# WallPhish.net
KiCad netlist of a schematic drawn in Altium Designer
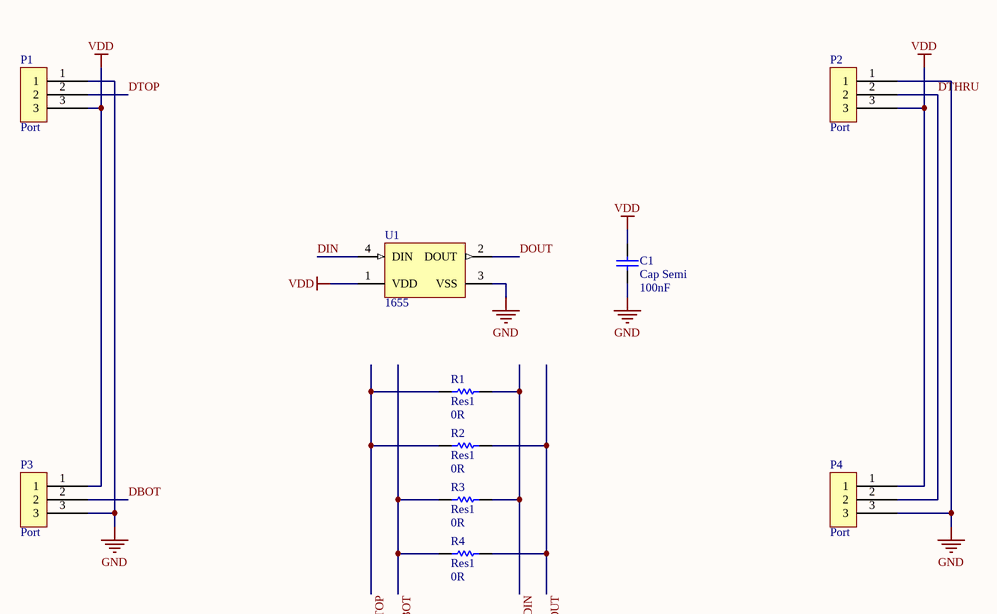
[diagram p0: WallPhish.SchDoc]

(export (version "E")
  (design (tool "Eeschema 10.0.6"))
  (components
    (comp (ref "C1")
      (value "Cap Semi")
      (footprint "C1206")
      (description "Capacitor (Semiconductor SIM Model)")
      (fields (field (name "ALTIUM_VALUE") "100nF") (field (name "PUBLISHER") "Altium Limited"))
      (libsource (lib "Miscellaneous Devices") (part "Cap Semi"))
    )
    (comp (ref "P1")
      (value "Port")
      (footprint "Port-3wire")
      (description "3-wire port")
      (libsource (lib "Port-3wire") (part "Port"))
    )
    (comp (ref "P2")
      (value "Port")
      (footprint "Port-3wire")
      (description "3-wire port")
      (libsource (lib "Port-3wire") (part "Port"))
    )
    (comp (ref "P3")
      (value "Port")
      (footprint "Port-3wire")
      (description "3-wire port")
      (libsource (lib "Port-3wire") (part "Port"))
    )
    (comp (ref "P4")
      (value "Port")
      (footprint "Port-3wire")
      (description "3-wire port")
      (libsource (lib "Port-3wire") (part "Port"))
    )
    (comp (ref "R1")
      (value "Res1")
      (footprint "C1206")
      (description "Resistor")
      (fields (field (name "ALTIUM_VALUE") "0R") (field (name "PUBLISHER") "Altium Limited"))
      (libsource (lib "Miscellaneous Devices") (part "Res1"))
    )
    (comp (ref "R2")
      (value "Res1")
      (footprint "C1206")
      (description "Resistor")
      (fields (field (name "ALTIUM_VALUE") "0R") (field (name "PUBLISHER") "Altium Limited"))
      (libsource (lib "Miscellaneous Devices") (part "Res1"))
    )
    (comp (ref "R3")
      (value "Res1")
      (footprint "C1206")
      (description "Resistor")
      (fields (field (name "ALTIUM_VALUE") "0R") (field (name "PUBLISHER") "Altium Limited"))
      (libsource (lib "Miscellaneous Devices") (part "Res1"))
    )
    (comp (ref "R4")
      (value "Res1")
      (footprint "C1206")
      (description "Resistor")
      (fields (field (name "ALTIUM_VALUE") "0R") (field (name "PUBLISHER") "Altium Limited"))
      (libsource (lib "Miscellaneous Devices") (part "Res1"))
    )
    (comp (ref "U1")
      (value "1655")
      (footprint "ADA-RGB-1655_V")
      (fields (field (name "MANUFACTURER") "Adafruit-Industries-LLC"))
      (libsource (lib "Altium Content Vault") (part "ADA-RGB-1655-4"))
    )
  )
  (nets
    (net (code "1") (name "/DBOT") (class "Default")
      (node (ref "P3") (pin "2") (pinfunction "2_2") (pintype "passive"))
      (node (ref "R3") (pin "1") (pinfunction "1_1") (pintype "passive"))
      (node (ref "R4") (pin "1") (pinfunction "1_1") (pintype "passive"))
    )
    (net (code "2") (name "/DIN") (class "Default")
      (node (ref "R1") (pin "2") (pinfunction "2_2") (pintype "passive"))
      (node (ref "R3") (pin "2") (pinfunction "2_2") (pintype "passive"))
      (node (ref "U1") (pin "4") (pinfunction "DIN_4") (pintype "input"))
    )
    (net (code "3") (name "/DOUT") (class "Default")
      (node (ref "R2") (pin "2") (pinfunction "2_2") (pintype "passive"))
      (node (ref "R4") (pin "2") (pinfunction "2_2") (pintype "passive"))
      (node (ref "U1") (pin "2") (pinfunction "DOUT_2") (pintype "output"))
    )
    (net (code "4") (name "/DTHRU") (class "Default")
      (node (ref "P2") (pin "2") (pinfunction "2_2") (pintype "passive"))
      (node (ref "P4") (pin "2") (pinfunction "2_2") (pintype "passive"))
    )
    (net (code "5") (name "/DTOP") (class "Default")
      (node (ref "P1") (pin "2") (pinfunction "2_2") (pintype "passive"))
      (node (ref "R1") (pin "1") (pinfunction "1_1") (pintype "passive"))
      (node (ref "R2") (pin "1") (pinfunction "1_1") (pintype "passive"))
    )
    (net (code "6") (name "GND") (class "Default")
      (node (ref "C1") (pin "1") (pinfunction "1_1") (pintype "passive"))
      (node (ref "P1") (pin "1") (pinfunction "1_1") (pintype "passive"))
      (node (ref "P2") (pin "1") (pinfunction "1_1") (pintype "passive"))
      (node (ref "P3") (pin "3") (pinfunction "3_3") (pintype "passive"))
      (node (ref "P4") (pin "3") (pinfunction "3_3") (pintype "passive"))
      (node (ref "U1") (pin "3") (pinfunction "VSS_3") (pintype "power_in"))
    )
    (net (code "7") (name "VDD") (class "Default")
      (node (ref "C1") (pin "2") (pinfunction "2_2") (pintype "passive"))
      (node (ref "P1") (pin "3") (pinfunction "3_3") (pintype "passive"))
      (node (ref "P2") (pin "3") (pinfunction "3_3") (pintype "passive"))
      (node (ref "P3") (pin "1") (pinfunction "1_1") (pintype "passive"))
      (node (ref "P4") (pin "1") (pinfunction "1_1") (pintype "passive"))
      (node (ref "U1") (pin "1") (pinfunction "VDD_1") (pintype "power_in"))
    )
  )
)
